# OBI_SlaveBoard_final.net
KiCad netlist of a schematic drawn in EAGLE
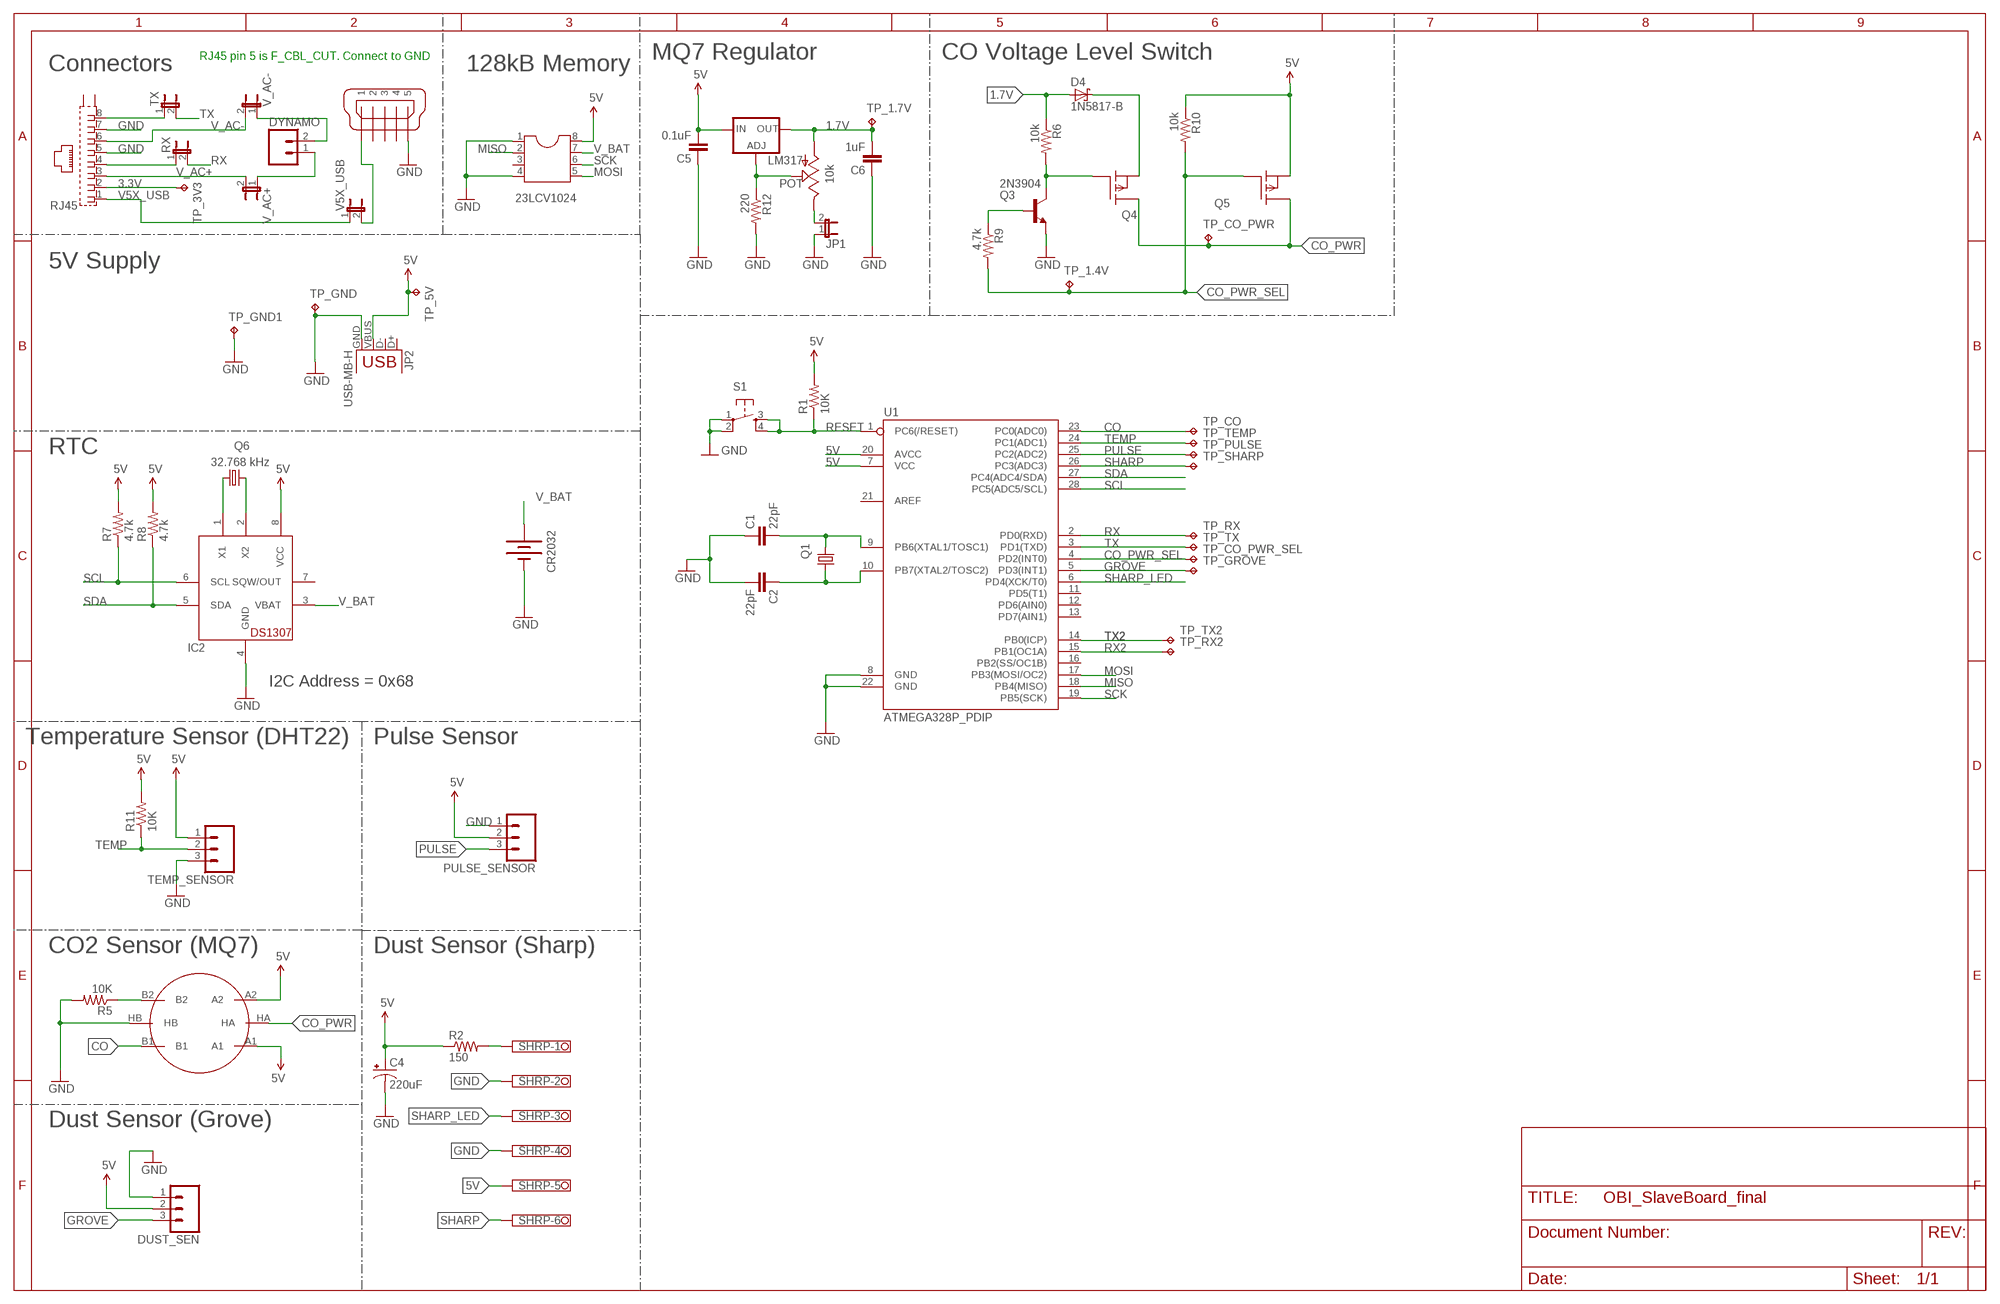
[diagram p0: schematic, sheet 1]

(export (version "E")
  (design (tool "Eeschema 10.0.6"))
  (components
    (comp (ref "23LCV1024")
      (value "DIL8S")
      (footprint "eagle-import:SOCKET-08")
      (libsource (lib "eagle-import") (part "DIL8S"))
    )
    (comp (ref "C1")
      (value "22pF")
      (footprint "eagle-import:C025-024X044")
      (libsource (lib "eagle-import") (part "C-EU025-024X044"))
    )
    (comp (ref "C2")
      (value "22pF")
      (footprint "eagle-import:C025-024X044")
      (libsource (lib "eagle-import") (part "C-EU025-024X044"))
    )
    (comp (ref "C4")
      (value "220uF")
      (footprint "eagle-import:CPOL-RADIAL-10UF-25V")
      (libsource (lib "eagle-import") (part "CAP_POLPTH2"))
    )
    (comp (ref "C5")
      (value "0.1uF")
      (footprint "eagle-import:C025-024X044")
      (libsource (lib "eagle-import") (part "C-EU025-024X044"))
    )
    (comp (ref "C6")
      (value "1uF")
      (footprint "eagle-import:C025-024X044")
      (libsource (lib "eagle-import") (part "C-EU025-024X044"))
    )
    (comp (ref "CO2_SENSOR")
      (value "METHANE_SENSOR")
      (footprint "eagle-import:MQ-3")
      (libsource (lib "eagle-import") (part "METHANE_SENSOR"))
    )
    (comp (ref "CR2032")
      (value "BATTERY20PTH")
      (footprint "eagle-import:BATTCOM_20MM_PTH")
      (libsource (lib "eagle-import") (part "BATTERY20PTH"))
    )
    (comp (ref "D4")
      (value "1N5817-B")
      (footprint "eagle-import:DO41-10")
      (libsource (lib "eagle-import") (part "SCHOTTKY-DIODEDO41"))
    )
    (comp (ref "DUST_SEN")
      (value "M03SCREW")
      (footprint "eagle-import:SCREWTERMINAL-3.5MM-3")
      (libsource (lib "eagle-import") (part "M03SCREW"))
    )
    (comp (ref "DYNAMO")
      (value "M023.5MM")
      (footprint "eagle-import:SCREWTERMINAL-3.5MM-2")
      (libsource (lib "eagle-import") (part "M023.5MM"))
    )
    (comp (ref "IC2")
      (value "DS1307")
      (footprint "eagle-import:DIL08")
      (libsource (lib "eagle-import") (part "DS1307"))
    )
    (comp (ref "JP1")
      (value "JP1E")
      (footprint "eagle-import:JP1")
      (libsource (lib "eagle-import") (part "JP1E"))
    )
    (comp (ref "JP2")
      (value "USB-MB-H")
      (footprint "eagle-import:USB-MB-H")
      (libsource (lib "eagle-import") (part "USB-MB-H"))
    )
    (comp (ref "LM317")
      (value "LM317TS")
      (footprint "eagle-import:317TS")
      (libsource (lib "eagle-import") (part "LM317TS"))
    )
    (comp (ref "MICROB")
      (value "MICRO-USB-ZX62R-B-5P")
      (footprint "eagle-import:ZX62R-B-5P")
      (libsource (lib "eagle-import") (part "MICRO-USB-ZX62R-B-5P"))
    )
    (comp (ref "POT")
      (value "10k")
      (footprint "eagle-import:CT6")
      (libsource (lib "eagle-import") (part "TRIM_US-CT6"))
    )
    (comp (ref "PULSE_SENSOR")
      (value "M03SCREW")
      (footprint "eagle-import:SCREWTERMINAL-3.5MM-3")
      (libsource (lib "eagle-import") (part "M03SCREW"))
    )
    (comp (ref "Q1")
      (value "CRYSTALHC49S")
      (footprint "eagle-import:HC49_S")
      (libsource (lib "eagle-import") (part "CRYSTALHC49S"))
    )
    (comp (ref "Q3")
      (value "2N3904")
      (footprint "eagle-import:TO-92")
      (libsource (lib "eagle-import") (part "TRANSISTOR_NPN2N3904"))
    )
    (comp (ref "Q4")
      (value "BSS110")
      (footprint "eagle-import:TO92")
      (libsource (lib "eagle-import") (part "BSS110"))
    )
    (comp (ref "Q5")
      (value "BSS110")
      (footprint "eagle-import:TO92")
      (libsource (lib "eagle-import") (part "BSS110"))
    )
    (comp (ref "Q6")
      (value "32.768 kHz")
      (footprint "eagle-import:TC26V")
      (libsource (lib "eagle-import") (part "CRYSTALTC26V"))
    )
    (comp (ref "R1")
      (value "10K")
      (footprint "eagle-import:0207_2V")
      (libsource (lib "eagle-import") (part "R-US_0207/2V"))
    )
    (comp (ref "R2")
      (value "150")
      (footprint "eagle-import:0207_2V")
      (libsource (lib "eagle-import") (part "R-US_0207/2V"))
    )
    (comp (ref "R5")
      (value "10K")
      (footprint "eagle-import:0207_2V")
      (libsource (lib "eagle-import") (part "R-US_0207/2V"))
    )
    (comp (ref "R6")
      (value "10k")
      (footprint "eagle-import:0207_2V")
      (libsource (lib "eagle-import") (part "R-US_0207/2V"))
    )
    (comp (ref "R7")
      (value "4.7k")
      (footprint "eagle-import:0207_2V")
      (libsource (lib "eagle-import") (part "R-US_0207/2V"))
    )
    (comp (ref "R8")
      (value "4.7k")
      (footprint "eagle-import:0207_2V")
      (libsource (lib "eagle-import") (part "R-US_0207/2V"))
    )
    (comp (ref "R9")
      (value "4.7k")
      (footprint "eagle-import:0207_2V")
      (libsource (lib "eagle-import") (part "R-US_0207/2V"))
    )
    (comp (ref "R10")
      (value "10k")
      (footprint "eagle-import:0207_2V")
      (libsource (lib "eagle-import") (part "R-US_0207/2V"))
    )
    (comp (ref "R11")
      (value "10K")
      (footprint "eagle-import:0207_2V")
      (libsource (lib "eagle-import") (part "R-US_0207/2V"))
    )
    (comp (ref "R12")
      (value "220")
      (footprint "eagle-import:0207_2V")
      (libsource (lib "eagle-import") (part "R-US_0207/2V"))
    )
    (comp (ref "RJ45")
      (value "0446200002")
      (footprint "eagle-import:0446200002")
      (fields (field (name "MF") "MOLEX"))
      (libsource (lib "eagle-import") (part "0446200002"))
    )
    (comp (ref "RX")
      (value "JP1E")
      (footprint "eagle-import:JP1")
      (libsource (lib "eagle-import") (part "JP1E"))
    )
    (comp (ref "S1")
      (value "TAC_SWITCHPTH")
      (footprint "eagle-import:TACTILE-PTH")
      (libsource (lib "eagle-import") (part "TAC_SWITCHPTH"))
    )
    (comp (ref "SHRP")
      (value "1751280")
      (footprint "eagle-import:1751280")
      (libsource (lib "eagle-import") (part "1751280"))
    )
    (comp (ref "TEMP_SENSOR")
      (value "M03SCREW")
      (footprint "eagle-import:SCREWTERMINAL-3.5MM-3")
      (libsource (lib "eagle-import") (part "M03SCREW"))
    )
    (comp (ref "TP_1.4V")
      (value "TPPAD1-13")
      (footprint "eagle-import:P1-13")
      (libsource (lib "eagle-import") (part "TPPAD1-13"))
    )
    (comp (ref "TP_1.7V")
      (value "TPPAD1-13")
      (footprint "eagle-import:P1-13")
      (libsource (lib "eagle-import") (part "TPPAD1-13"))
    )
    (comp (ref "TP_3V3")
      (value "TPPAD1-13")
      (footprint "eagle-import:P1-13")
      (libsource (lib "eagle-import") (part "TPPAD1-13"))
    )
    (comp (ref "TP_5V")
      (value "TPPAD1-13")
      (footprint "eagle-import:P1-13")
      (libsource (lib "eagle-import") (part "TPPAD1-13"))
    )
    (comp (ref "TP_CO")
      (value "TPPAD1-13")
      (footprint "eagle-import:P1-13")
      (libsource (lib "eagle-import") (part "TPPAD1-13"))
    )
    (comp (ref "TP_CO_PWR")
      (value "TPPAD1-13")
      (footprint "eagle-import:P1-13")
      (libsource (lib "eagle-import") (part "TPPAD1-13"))
    )
    (comp (ref "TP_CO_PWR_SEL")
      (value "TPPAD1-13")
      (footprint "eagle-import:P1-13")
      (libsource (lib "eagle-import") (part "TPPAD1-13"))
    )
    (comp (ref "TP_GND")
      (value "TPPAD1-13")
      (footprint "eagle-import:P1-13")
      (libsource (lib "eagle-import") (part "TPPAD1-13"))
    )
    (comp (ref "TP_GND1")
      (value "TPPAD1-13")
      (footprint "eagle-import:P1-13")
      (libsource (lib "eagle-import") (part "TPPAD1-13"))
    )
    (comp (ref "TP_GROVE")
      (value "TPPAD1-13")
      (footprint "eagle-import:P1-13")
      (libsource (lib "eagle-import") (part "TPPAD1-13"))
    )
    (comp (ref "TP_PULSE")
      (value "TPPAD1-13")
      (footprint "eagle-import:P1-13")
      (libsource (lib "eagle-import") (part "TPPAD1-13"))
    )
    (comp (ref "TP_RX")
      (value "TPPAD1-13")
      (footprint "eagle-import:P1-13")
      (libsource (lib "eagle-import") (part "TPPAD1-13"))
    )
    (comp (ref "TP_RX2")
      (value "TPPAD1-13")
      (footprint "eagle-import:P1-13")
      (libsource (lib "eagle-import") (part "TPPAD1-13"))
    )
    (comp (ref "TP_SHARP")
      (value "TPPAD1-13")
      (footprint "eagle-import:P1-13")
      (libsource (lib "eagle-import") (part "TPPAD1-13"))
    )
    (comp (ref "TP_TEMP")
      (value "TPPAD1-13")
      (footprint "eagle-import:P1-13")
      (libsource (lib "eagle-import") (part "TPPAD1-13"))
    )
    (comp (ref "TP_TX")
      (value "TPPAD1-13")
      (footprint "eagle-import:P1-13")
      (libsource (lib "eagle-import") (part "TPPAD1-13"))
    )
    (comp (ref "TP_TX2")
      (value "TPPAD1-13")
      (footprint "eagle-import:P1-13")
      (libsource (lib "eagle-import") (part "TPPAD1-13"))
    )
    (comp (ref "TX")
      (value "JP1E")
      (footprint "eagle-import:JP1")
      (libsource (lib "eagle-import") (part "JP1E"))
    )
    (comp (ref "U1")
      (value "ATMEGA328P_PDIP")
      (footprint "eagle-import:DIL28-3")
      (libsource (lib "eagle-import") (part "ATMEGA328P_PDIP"))
    )
    (comp (ref "V5X_USB")
      (value "JP1E")
      (footprint "eagle-import:JP1")
      (libsource (lib "eagle-import") (part "JP1E"))
    )
    (comp (ref "V_AC+")
      (value "JP1E")
      (footprint "eagle-import:JP1")
      (libsource (lib "eagle-import") (part "JP1E"))
    )
    (comp (ref "V_AC-")
      (value "JP1E")
      (footprint "eagle-import:JP1")
      (libsource (lib "eagle-import") (part "JP1E"))
    )
  )
  (nets
    (net (code "1") (name "/3.3V") (class "Default")
      (node (ref "RJ45") (pin "2") (pinfunction "2_2") (pintype "passive"))
      (node (ref "TP_3V3") (pin "TP") (pinfunction "TP_TP") (pintype "input"))
    )
    (net (code "2") (name "/MISO") (class "Default")
      (node (ref "23LCV1024") (pin "2") (pinfunction "2_2") (pintype "passive"))
      (node (ref "U1") (pin "18") (pinfunction "PB4(MISO)_18") (pintype "bidirectional"))
    )
    (net (code "3") (name "/MOSI") (class "Default")
      (node (ref "23LCV1024") (pin "5") (pinfunction "5_5") (pintype "passive"))
      (node (ref "U1") (pin "17") (pinfunction "PB3(MOSI/OC2)_17") (pintype "bidirectional"))
    )
    (net (code "4") (name "/RESET") (class "Default")
      (node (ref "R1") (pin "1") (pinfunction "1_1") (pintype "passive"))
      (node (ref "S1") (pin "3") (pinfunction "3_3") (pintype "passive"))
      (node (ref "S1") (pin "4") (pinfunction "4_4") (pintype "passive"))
      (node (ref "U1") (pin "1") (pinfunction "PC6(/RESET)_1") (pintype "bidirectional"))
    )
    (net (code "5") (name "/RX") (class "Default")
      (node (ref "RX") (pin "2") (pinfunction "2_2") (pintype "passive"))
      (node (ref "TP_RX") (pin "TP") (pinfunction "TP_TP") (pintype "input"))
      (node (ref "U1") (pin "2") (pinfunction "PD0(RXD)_2") (pintype "bidirectional"))
    )
    (net (code "6") (name "/RX2") (class "Default")
      (node (ref "TP_RX2") (pin "TP") (pinfunction "TP_TP") (pintype "input"))
      (node (ref "U1") (pin "15") (pinfunction "PB1(OC1A)_15") (pintype "bidirectional"))
    )
    (net (code "7") (name "/SCK") (class "Default")
      (node (ref "23LCV1024") (pin "6") (pinfunction "6_6") (pintype "passive"))
      (node (ref "U1") (pin "19") (pinfunction "PB5(SCK)_19") (pintype "bidirectional"))
    )
    (net (code "8") (name "/SCL") (class "Default")
      (node (ref "IC2") (pin "6") (pinfunction "SCL_6") (pintype "bidirectional"))
      (node (ref "R7") (pin "1") (pinfunction "1_1") (pintype "passive"))
      (node (ref "U1") (pin "28") (pinfunction "PC5(ADC5/SCL)_28") (pintype "bidirectional"))
    )
    (net (code "9") (name "/SDA") (class "Default")
      (node (ref "IC2") (pin "5") (pinfunction "SDA_5") (pintype "bidirectional"))
      (node (ref "R8") (pin "1") (pinfunction "1_1") (pintype "passive"))
      (node (ref "U1") (pin "27") (pinfunction "PC4(ADC4/SDA)_27") (pintype "bidirectional"))
    )
    (net (code "10") (name "/TEMP") (class "Default")
      (node (ref "R11") (pin "1") (pinfunction "1_1") (pintype "passive"))
      (node (ref "TEMP_SENSOR") (pin "2") (pinfunction "2_2") (pintype "passive"))
      (node (ref "TP_TEMP") (pin "TP") (pinfunction "TP_TP") (pintype "input"))
      (node (ref "U1") (pin "24") (pinfunction "PC1(ADC1)_24") (pintype "bidirectional"))
    )
    (net (code "11") (name "/TX") (class "Default")
      (node (ref "TP_TX") (pin "TP") (pinfunction "TP_TP") (pintype "input"))
      (node (ref "TX") (pin "2") (pinfunction "2_2") (pintype "passive"))
      (node (ref "U1") (pin "3") (pinfunction "PD1(TXD)_3") (pintype "bidirectional"))
    )
    (net (code "12") (name "/TX2") (class "Default")
      (node (ref "TP_TX2") (pin "TP") (pinfunction "TP_TP") (pintype "input"))
      (node (ref "U1") (pin "14") (pinfunction "PB0(ICP)_14") (pintype "bidirectional"))
    )
    (net (code "13") (name "/V5X_USB") (class "Default")
      (node (ref "RJ45") (pin "1") (pinfunction "1_1") (pintype "passive"))
      (node (ref "V5X_USB") (pin "1") (pinfunction "1_1") (pintype "passive"))
    )
    (net (code "14") (name "/V_AC+") (class "Default")
      (node (ref "RJ45") (pin "3") (pinfunction "3_3") (pintype "passive"))
      (node (ref "V_AC+") (pin "2") (pinfunction "2_2") (pintype "passive"))
    )
    (net (code "15") (name "/V_AC-") (class "Default")
      (node (ref "RJ45") (pin "6") (pinfunction "6_6") (pintype "passive"))
      (node (ref "V_AC-") (pin "2") (pinfunction "2_2") (pintype "passive"))
    )
    (net (code "16") (name "/V_BAT") (class "Default")
      (node (ref "23LCV1024") (pin "7") (pinfunction "7_7") (pintype "passive"))
      (node (ref "CR2032") (pin "1") (pinfunction "+_1") (pintype "power_in"))
      (node (ref "IC2") (pin "3") (pinfunction "VBAT_3") (pintype "power_in"))
    )
    (net (code "17") (name "1.7V") (class "Default")
      (node (ref "C6") (pin "2") (pinfunction "2_2") (pintype "passive"))
      (node (ref "D4") (pin "A") (pinfunction "A_A") (pintype "passive"))
      (node (ref "LM317") (pin "2") (pinfunction "OUT_2") (pintype "passive"))
      (node (ref "POT") (pin "A") (pinfunction "A_A") (pintype "passive"))
      (node (ref "R6") (pin "1") (pinfunction "1_1") (pintype "passive"))
      (node (ref "TP_1.7V") (pin "TP") (pinfunction "TP_TP") (pintype "input"))
    )
    (net (code "18") (name "5V") (class "Default")
      (node (ref "23LCV1024") (pin "8") (pinfunction "8_8") (pintype "passive"))
      (node (ref "C4") (pin "1") (pinfunction "+_1") (pintype "passive"))
      (node (ref "C5") (pin "2") (pinfunction "2_2") (pintype "passive"))
      (node (ref "CO2_SENSOR") (pin "A1") (pinfunction "A1_A1") (pintype "bidirectional"))
      (node (ref "CO2_SENSOR") (pin "A2") (pinfunction "A2_A2") (pintype "bidirectional"))
      (node (ref "DUST_SEN") (pin "2") (pinfunction "2_2") (pintype "passive"))
      (node (ref "IC2") (pin "8") (pinfunction "VCC_8") (pintype "power_in"))
      (node (ref "JP2") (pin "VBUS") (pinfunction "VBUS_VBUS") (pintype "bidirectional"))
      (node (ref "LM317") (pin "3") (pinfunction "IN_3") (pintype "input"))
      (node (ref "PULSE_SENSOR") (pin "2") (pinfunction "2_2") (pintype "passive"))
      (node (ref "Q5") (pin "1") (pinfunction "S_1") (pintype "passive"))
      (node (ref "R1") (pin "2") (pinfunction "2_2") (pintype "passive"))
      (node (ref "R10") (pin "1") (pinfunction "1_1") (pintype "passive"))
      (node (ref "R11") (pin "2") (pinfunction "2_2") (pintype "passive"))
      (node (ref "R2") (pin "1") (pinfunction "1_1") (pintype "passive"))
      (node (ref "R7") (pin "2") (pinfunction "2_2") (pintype "passive"))
      (node (ref "R8") (pin "2") (pinfunction "2_2") (pintype "passive"))
      (node (ref "SHRP") (pin "5") (pinfunction "K_5") (pintype "passive"))
      (node (ref "TEMP_SENSOR") (pin "1") (pinfunction "1_1") (pintype "passive"))
      (node (ref "TP_5V") (pin "TP") (pinfunction "TP_TP") (pintype "input"))
      (node (ref "U1") (pin "20") (pinfunction "AVCC_20") (pintype "bidirectional"))
      (node (ref "U1") (pin "7") (pinfunction "VCC_7") (pintype "bidirectional"))
    )
    (net (code "19") (name "CO") (class "Default")
      (node (ref "CO2_SENSOR") (pin "B1") (pinfunction "B1_B1") (pintype "bidirectional"))
      (node (ref "TP_CO") (pin "TP") (pinfunction "TP_TP") (pintype "input"))
      (node (ref "U1") (pin "23") (pinfunction "PC0(ADC0)_23") (pintype "bidirectional"))
    )
    (net (code "20") (name "CO_PWR") (class "Default")
      (node (ref "CO2_SENSOR") (pin "HA") (pinfunction "HA_HA") (pintype "bidirectional"))
      (node (ref "Q4") (pin "3") (pinfunction "D_3") (pintype "passive"))
      (node (ref "Q5") (pin "3") (pinfunction "D_3") (pintype "passive"))
      (node (ref "TP_CO_PWR") (pin "TP") (pinfunction "TP_TP") (pintype "input"))
    )
    (net (code "21") (name "CO_PWR_SEL") (class "Default")
      (node (ref "Q5") (pin "2") (pinfunction "G_2") (pintype "passive"))
      (node (ref "R10") (pin "2") (pinfunction "2_2") (pintype "passive"))
      (node (ref "R9") (pin "2") (pinfunction "2_2") (pintype "passive"))
      (node (ref "TP_1.4V") (pin "TP") (pinfunction "TP_TP") (pintype "input"))
      (node (ref "TP_CO_PWR_SEL") (pin "TP") (pinfunction "TP_TP") (pintype "input"))
      (node (ref "U1") (pin "4") (pinfunction "PD2(INT0)_4") (pintype "bidirectional"))
    )
    (net (code "22") (name "GND") (class "Default")
      (node (ref "23LCV1024") (pin "1") (pinfunction "1_1") (pintype "passive"))
      (node (ref "23LCV1024") (pin "4") (pinfunction "4_4") (pintype "passive"))
      (node (ref "C1") (pin "1") (pinfunction "1_1") (pintype "passive"))
      (node (ref "C2") (pin "2") (pinfunction "2_2") (pintype "passive"))
      (node (ref "C4") (pin "2") (pinfunction "-_2") (pintype "passive"))
      (node (ref "C5") (pin "1") (pinfunction "1_1") (pintype "passive"))
      (node (ref "C6") (pin "1") (pinfunction "1_1") (pintype "passive"))
      (node (ref "CO2_SENSOR") (pin "HB") (pinfunction "HB_HB") (pintype "bidirectional"))
      (node (ref "CR2032") (pin "2") (pinfunction "-_2") (pintype "power_in"))
      (node (ref "DUST_SEN") (pin "1") (pinfunction "1_1") (pintype "passive"))
      (node (ref "IC2") (pin "4") (pinfunction "GND_4") (pintype "power_in"))
      (node (ref "JP1") (pin "1") (pinfunction "1_1") (pintype "passive"))
      (node (ref "JP2") (pin "GND") (pinfunction "GND_GND") (pintype "bidirectional"))
      (node (ref "MICROB") (pin "5") (pinfunction "5_5") (pintype "input"))
      (node (ref "PULSE_SENSOR") (pin "1") (pinfunction "1_1") (pintype "passive"))
      (node (ref "Q3") (pin "1") (pinfunction "E_1") (pintype "passive"))
      (node (ref "R12") (pin "2") (pinfunction "2_2") (pintype "passive"))
      (node (ref "R5") (pin "2") (pinfunction "2_2") (pintype "passive"))
      (node (ref "RJ45") (pin "5") (pinfunction "5_5") (pintype "passive"))
      (node (ref "RJ45") (pin "7") (pinfunction "7_7") (pintype "passive"))
      (node (ref "S1") (pin "1") (pinfunction "1_1") (pintype "passive"))
      (node (ref "S1") (pin "2") (pinfunction "2_2") (pintype "passive"))
      (node (ref "SHRP") (pin "2") (pinfunction "K_2") (pintype "passive"))
      (node (ref "SHRP") (pin "4") (pinfunction "K_4") (pintype "passive"))
      (node (ref "TEMP_SENSOR") (pin "3") (pinfunction "3_3") (pintype "passive"))
      (node (ref "TP_GND") (pin "TP") (pinfunction "TP_TP") (pintype "input"))
      (node (ref "TP_GND1") (pin "TP") (pinfunction "TP_TP") (pintype "input"))
      (node (ref "U1") (pin "22") (pinfunction "GND_22") (pintype "bidirectional"))
      (node (ref "U1") (pin "8") (pinfunction "GND_8") (pintype "bidirectional"))
    )
    (net (code "23") (name "GROVE") (class "Default")
      (node (ref "DUST_SEN") (pin "3") (pinfunction "3_3") (pintype "passive"))
      (node (ref "TP_GROVE") (pin "TP") (pinfunction "TP_TP") (pintype "input"))
      (node (ref "U1") (pin "5") (pinfunction "PD3(INT1)_5") (pintype "bidirectional"))
    )
    (net (code "24") (name "Net-(CO2_SENSOR-PadB2)") (class "Default")
      (node (ref "CO2_SENSOR") (pin "B2") (pinfunction "B2_B2") (pintype "bidirectional"))
      (node (ref "R5") (pin "1") (pinfunction "1_1") (pintype "passive"))
    )
    (net (code "25") (name "Net-(DYNAMO-Pad1)") (class "Default")
      (node (ref "DYNAMO") (pin "1") (pinfunction "1_1") (pintype "passive"))
      (node (ref "V_AC+") (pin "1") (pinfunction "1_1") (pintype "passive"))
    )
    (net (code "26") (name "Net-(DYNAMO-Pad2)") (class "Default")
      (node (ref "DYNAMO") (pin "2") (pinfunction "2_2") (pintype "passive"))
      (node (ref "V_AC-") (pin "1") (pinfunction "1_1") (pintype "passive"))
    )
    (net (code "27") (name "Net-(IC2-X1)") (class "Default")
      (node (ref "IC2") (pin "1") (pinfunction "X1_1") (pintype "passive"))
      (node (ref "Q6") (pin "1") (pinfunction "1_1") (pintype "passive"))
    )
    (net (code "28") (name "Net-(IC2-X2)") (class "Default")
      (node (ref "IC2") (pin "2") (pinfunction "X2_2") (pintype "passive"))
      (node (ref "Q6") (pin "2") (pinfunction "2_2") (pintype "passive"))
    )
    (net (code "29") (name "Net-(JP1-Pad2)") (class "Default")
      (node (ref "JP1") (pin "2") (pinfunction "2_2") (pintype "passive"))
      (node (ref "POT") (pin "E") (pinfunction "E_E") (pintype "passive"))
    )
    (net (code "30") (name "Net-(LM317-ADJ)") (class "Default")
      (node (ref "LM317") (pin "1") (pinfunction "ADJ_1") (pintype "input"))
      (node (ref "POT") (pin "S") (pinfunction "S_S") (pintype "passive"))
      (node (ref "R12") (pin "1") (pinfunction "1_1") (pintype "passive"))
    )
    (net (code "31") (name "Net-(MICROB-Pad1)") (class "Default")
      (node (ref "MICROB") (pin "1") (pinfunction "1_1") (pintype "input"))
      (node (ref "V5X_USB") (pin "2") (pinfunction "2_2") (pintype "passive"))
    )
    (net (code "32") (name "Net-(Q3-B)") (class "Default")
      (node (ref "Q3") (pin "2") (pinfunction "B_2") (pintype "passive"))
      (node (ref "R9") (pin "1") (pinfunction "1_1") (pintype "passive"))
    )
    (net (code "33") (name "Net-(Q3-C)") (class "Default")
      (node (ref "Q3") (pin "3") (pinfunction "C_3") (pintype "passive"))
      (node (ref "Q4") (pin "2") (pinfunction "G_2") (pintype "passive"))
      (node (ref "R6") (pin "2") (pinfunction "2_2") (pintype "passive"))
    )
    (net (code "34") (name "Net-(Q4-S)") (class "Default")
      (node (ref "D4") (pin "C") (pinfunction "C_C") (pintype "passive"))
      (node (ref "Q4") (pin "1") (pinfunction "S_1") (pintype "passive"))
    )
    (net (code "35") (name "Net-(RJ45-Pad4)") (class "Default")
      (node (ref "RJ45") (pin "4") (pinfunction "4_4") (pintype "passive"))
      (node (ref "RX") (pin "1") (pinfunction "1_1") (pintype "passive"))
    )
    (net (code "36") (name "Net-(RJ45-Pad8)") (class "Default")
      (node (ref "RJ45") (pin "8") (pinfunction "8_8") (pintype "passive"))
      (node (ref "TX") (pin "1") (pinfunction "1_1") (pintype "passive"))
    )
    (net (code "37") (name "Net-(SHRPA-K)") (class "Default")
      (node (ref "R2") (pin "2") (pinfunction "2_2") (pintype "passive"))
      (node (ref "SHRP") (pin "1") (pinfunction "K_1") (pintype "passive"))
    )
    (net (code "38") (name "Net-(U1-PB6(XTAL1{slash}TOSC1))") (class "Default")
      (node (ref "C1") (pin "2") (pinfunction "2_2") (pintype "passive"))
      (node (ref "Q1") (pin "2") (pinfunction "2_2") (pintype "passive"))
      (node (ref "U1") (pin "9") (pinfunction "PB6(XTAL1/TOSC1)_9") (pintype "bidirectional"))
    )
    (net (code "39") (name "Net-(U1-PB7(XTAL2{slash}TOSC2))") (class "Default")
      (node (ref "C2") (pin "1") (pinfunction "1_1") (pintype "passive"))
      (node (ref "Q1") (pin "1") (pinfunction "1_1") (pintype "passive"))
      (node (ref "U1") (pin "10") (pinfunction "PB7(XTAL2/TOSC2)_10") (pintype "bidirectional"))
    )
    (net (code "40") (name "PULSE") (class "Default")
      (node (ref "PULSE_SENSOR") (pin "3") (pinfunction "3_3") (pintype "passive"))
      (node (ref "TP_PULSE") (pin "TP") (pinfunction "TP_TP") (pintype "input"))
      (node (ref "U1") (pin "25") (pinfunction "PC2(ADC2)_25") (pintype "bidirectional"))
    )
    (net (code "41") (name "SHARP") (class "Default")
      (node (ref "SHRP") (pin "6") (pinfunction "K_6") (pintype "passive"))
      (node (ref "TP_SHARP") (pin "TP") (pinfunction "TP_TP") (pintype "input"))
      (node (ref "U1") (pin "26") (pinfunction "PC3(ADC3)_26") (pintype "bidirectional"))
    )
    (net (code "42") (name "SHARP_LED") (class "Default")
      (node (ref "SHRP") (pin "3") (pinfunction "K_3") (pintype "passive"))
      (node (ref "U1") (pin "6") (pinfunction "PD4(XCK/T0)_6") (pintype "bidirectional"))
    )
    (net (code "43") (name "unconnected-(23LCV1024-Pad3)") (class "Default")
      (node (ref "23LCV1024") (pin "3") (pinfunction "3_3") (pintype "passive"))
    )
    (net (code "44") (name "unconnected-(IC2-SQW{slash}OUT-Pad7)") (class "Default")
      (node (ref "IC2") (pin "7") (pinfunction "SQW/OUT_7") (pintype "bidirectional"))
    )
    (net (code "45") (name "unconnected-(JP2-PadD+)") (class "Default")
      (node (ref "JP2") (pin "D+") (pinfunction "D+_D+") (pintype "bidirectional"))
    )
    (net (code "46") (name "unconnected-(JP2-PadD-)") (class "Default")
      (node (ref "JP2") (pin "D-") (pinfunction "D-_D-") (pintype "bidirectional"))
    )
    (net (code "47") (name "unconnected-(MICROB-Pad2)") (class "Default")
      (node (ref "MICROB") (pin "2") (pinfunction "2_2") (pintype "input"))
    )
    (net (code "48") (name "unconnected-(MICROB-Pad3)") (class "Default")
      (node (ref "MICROB") (pin "3") (pinfunction "3_3") (pintype "input"))
    )
    (net (code "49") (name "unconnected-(MICROB-Pad4)") (class "Default")
      (node (ref "MICROB") (pin "4") (pinfunction "4_4") (pintype "input"))
    )
    (net (code "50") (name "unconnected-(RJ45-S1-PadS@1)") (class "Default")
      (node (ref "RJ45") (pin "S@1") (pinfunction "S1_S@1") (pintype "passive"))
    )
    (net (code "51") (name "unconnected-(RJ45-S2-PadS@2)") (class "Default")
      (node (ref "RJ45") (pin "S@2") (pinfunction "S2_S@2") (pintype "passive"))
    )
    (net (code "52") (name "unconnected-(U1-AREF-Pad21)") (class "Default")
      (node (ref "U1") (pin "21") (pinfunction "AREF_21") (pintype "bidirectional"))
    )
    (net (code "53") (name "unconnected-(U1-PB2(SS{slash}OC1B)-Pad16)") (class "Default")
      (node (ref "U1") (pin "16") (pinfunction "PB2(SS/OC1B)_16") (pintype "bidirectional"))
    )
    (net (code "54") (name "unconnected-(U1-PD5(T1)-Pad11)") (class "Default")
      (node (ref "U1") (pin "11") (pinfunction "PD5(T1)_11") (pintype "bidirectional"))
    )
    (net (code "55") (name "unconnected-(U1-PD6(AIN0)-Pad12)") (class "Default")
      (node (ref "U1") (pin "12") (pinfunction "PD6(AIN0)_12") (pintype "bidirectional"))
    )
    (net (code "56") (name "unconnected-(U1-PD7(AIN1)-Pad13)") (class "Default")
      (node (ref "U1") (pin "13") (pinfunction "PD7(AIN1)_13") (pintype "bidirectional"))
    )
  )
)
